# TestPoints.net
KiCad netlist of a schematic drawn in Altium Designer
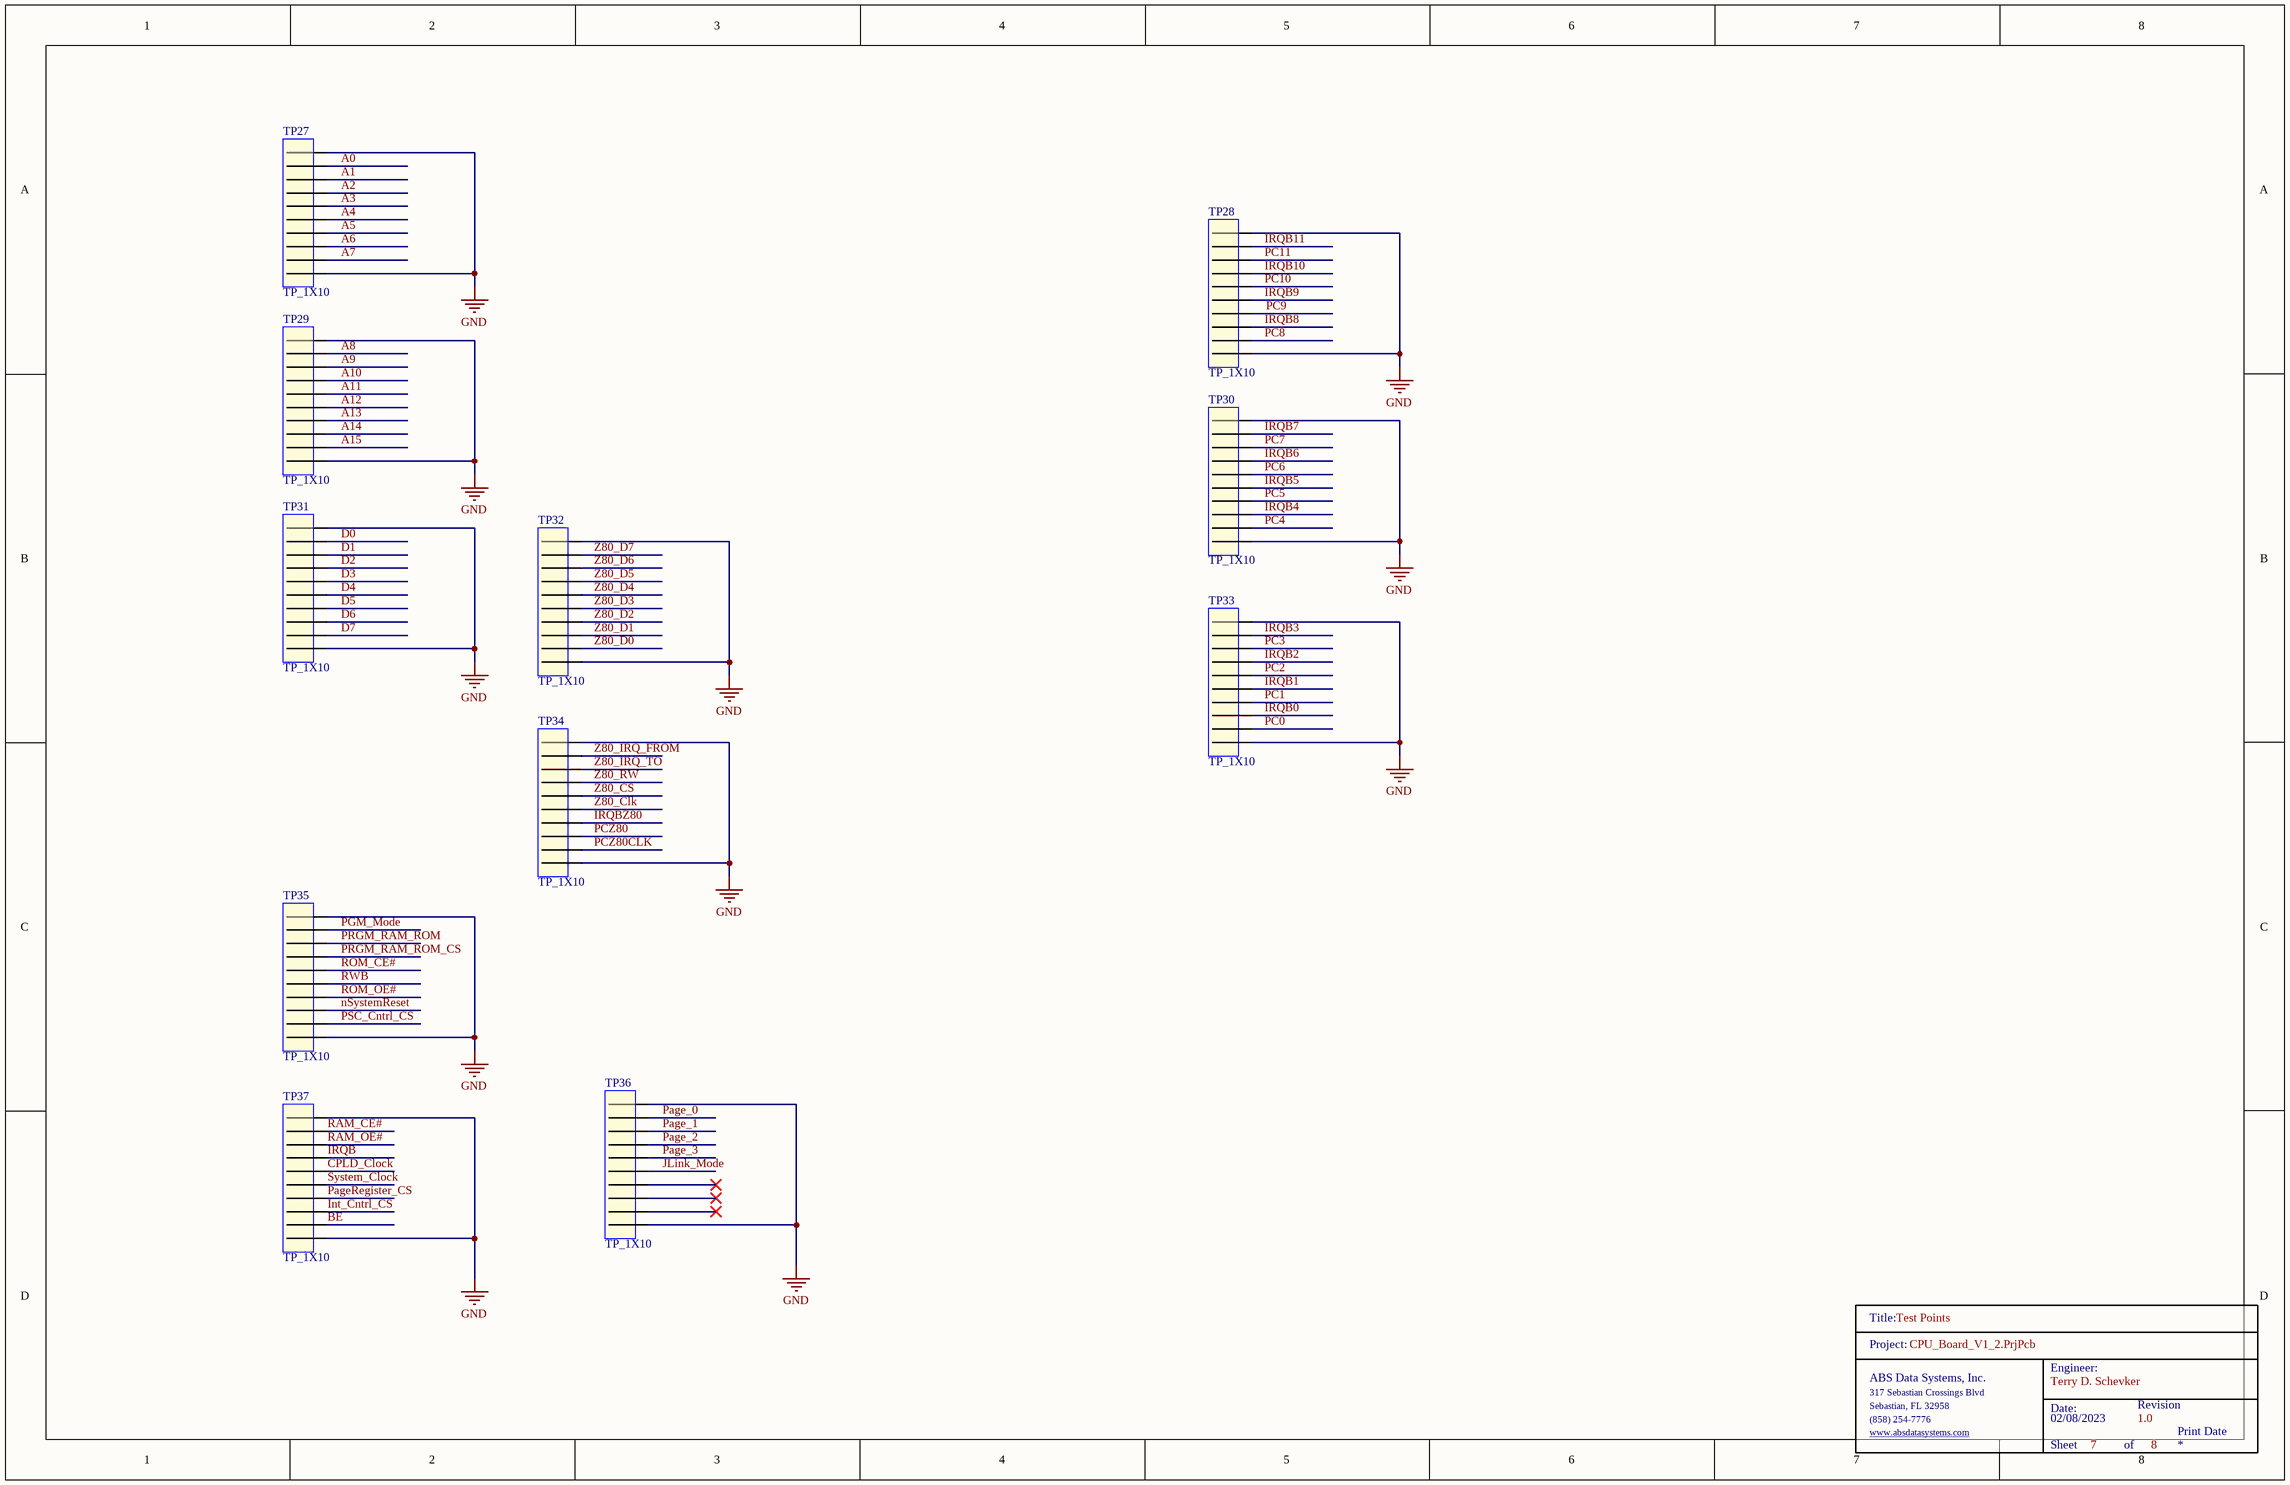
[diagram p0: TestPoints.SchDoc]

(export (version "E")
  (design (tool "Eeschema 10.0.6"))
  (components
    (comp (ref "TitleBlock_5") (value "TitleBlock") (libsource (lib "Misc") (part "TitleBlock")))
    (comp (ref "TP27")
      (value "TP_1X10")
      (footprint "TP_1X10")
      (fields
        (field (name "MANUFACTURER") "Samtec")
        (field (name "MANUFACTURER PART NUMBER") "TST-105-01-G-D")
      )
      (libsource (lib "Misc") (part "TP_1X10"))
    )
    (comp (ref "TP28")
      (value "TP_1X10")
      (footprint "TP_1X10")
      (fields
        (field (name "MANUFACTURER") "Samtec")
        (field (name "MANUFACTURER PART NUMBER") "TST-105-01-G-D")
      )
      (libsource (lib "Misc") (part "TP_1X10"))
    )
    (comp (ref "TP29")
      (value "TP_1X10")
      (footprint "TP_1X10")
      (fields
        (field (name "MANUFACTURER") "Samtec")
        (field (name "MANUFACTURER PART NUMBER") "TST-105-01-G-D")
      )
      (libsource (lib "Misc") (part "TP_1X10"))
    )
    (comp (ref "TP30")
      (value "TP_1X10")
      (footprint "TP_1X10")
      (fields
        (field (name "MANUFACTURER") "Samtec")
        (field (name "MANUFACTURER PART NUMBER") "TST-105-01-G-D")
      )
      (libsource (lib "Misc") (part "TP_1X10"))
    )
    (comp (ref "TP31")
      (value "TP_1X10")
      (footprint "TP_1X10")
      (fields
        (field (name "MANUFACTURER") "Samtec")
        (field (name "MANUFACTURER PART NUMBER") "TST-105-01-G-D")
      )
      (libsource (lib "Misc") (part "TP_1X10"))
    )
    (comp (ref "TP32")
      (value "TP_1X10")
      (footprint "TP_1X10")
      (fields
        (field (name "MANUFACTURER") "Samtec")
        (field (name "MANUFACTURER PART NUMBER") "TST-105-01-G-D")
      )
      (libsource (lib "Misc") (part "TP_1X10"))
    )
    (comp (ref "TP33")
      (value "TP_1X10")
      (footprint "TP_1X10")
      (fields
        (field (name "MANUFACTURER") "Samtec")
        (field (name "MANUFACTURER PART NUMBER") "TST-105-01-G-D")
      )
      (libsource (lib "Misc") (part "TP_1X10"))
    )
    (comp (ref "TP34")
      (value "TP_1X10")
      (footprint "TP_1X10")
      (fields
        (field (name "MANUFACTURER") "Samtec")
        (field (name "MANUFACTURER PART NUMBER") "TST-105-01-G-D")
      )
      (libsource (lib "Misc") (part "TP_1X10"))
    )
    (comp (ref "TP35")
      (value "TP_1X10")
      (footprint "TP_1X10")
      (fields
        (field (name "MANUFACTURER") "Samtec")
        (field (name "MANUFACTURER PART NUMBER") "TST-105-01-G-D")
      )
      (libsource (lib "Misc") (part "TP_1X10"))
    )
    (comp (ref "TP36")
      (value "TP_1X10")
      (footprint "TP_1X10")
      (fields
        (field (name "MANUFACTURER") "Samtec")
        (field (name "MANUFACTURER PART NUMBER") "TST-105-01-G-D")
      )
      (libsource (lib "Misc") (part "TP_1X10"))
    )
    (comp (ref "TP37")
      (value "TP_1X10")
      (footprint "TP_1X10")
      (fields
        (field (name "MANUFACTURER") "Samtec")
        (field (name "MANUFACTURER PART NUMBER") "TST-105-01-G-D")
      )
      (libsource (lib "Misc") (part "TP_1X10"))
    )
  )
  (nets
    (net (code "1") (name "/A0") (class "Default")
      (node (ref "TP27") (pin "2") (pinfunction "2_2") (pintype "passive"))
    )
    (net (code "2") (name "/A1") (class "Default")
      (node (ref "TP27") (pin "3") (pinfunction "3_3") (pintype "passive"))
    )
    (net (code "3") (name "/A2") (class "Default")
      (node (ref "TP27") (pin "4") (pinfunction "4_4") (pintype "passive"))
    )
    (net (code "4") (name "/A3") (class "Default")
      (node (ref "TP27") (pin "5") (pinfunction "5_5") (pintype "passive"))
    )
    (net (code "5") (name "/A4") (class "Default")
      (node (ref "TP27") (pin "6") (pinfunction "6_6") (pintype "passive"))
    )
    (net (code "6") (name "/A5") (class "Default")
      (node (ref "TP27") (pin "7") (pinfunction "7_7") (pintype "passive"))
    )
    (net (code "7") (name "/A6") (class "Default")
      (node (ref "TP27") (pin "8") (pinfunction "8_8") (pintype "passive"))
    )
    (net (code "8") (name "/A7") (class "Default")
      (node (ref "TP27") (pin "9") (pinfunction "9_9") (pintype "passive"))
    )
    (net (code "9") (name "/A8") (class "Default")
      (node (ref "TP29") (pin "2") (pinfunction "2_2") (pintype "passive"))
    )
    (net (code "10") (name "/A9") (class "Default")
      (node (ref "TP29") (pin "3") (pinfunction "3_3") (pintype "passive"))
    )
    (net (code "11") (name "/A10") (class "Default")
      (node (ref "TP29") (pin "4") (pinfunction "4_4") (pintype "passive"))
    )
    (net (code "12") (name "/A11") (class "Default")
      (node (ref "TP29") (pin "5") (pinfunction "5_5") (pintype "passive"))
    )
    (net (code "13") (name "/A12") (class "Default")
      (node (ref "TP29") (pin "6") (pinfunction "6_6") (pintype "passive"))
    )
    (net (code "14") (name "/A13") (class "Default")
      (node (ref "TP29") (pin "7") (pinfunction "7_7") (pintype "passive"))
    )
    (net (code "15") (name "/A14") (class "Default")
      (node (ref "TP29") (pin "8") (pinfunction "8_8") (pintype "passive"))
    )
    (net (code "16") (name "/A15") (class "Default")
      (node (ref "TP29") (pin "9") (pinfunction "9_9") (pintype "passive"))
    )
    (net (code "17") (name "/BE") (class "Default")
      (node (ref "TP37") (pin "9") (pinfunction "9_9") (pintype "passive"))
    )
    (net (code "18") (name "/CPLD_Clock") (class "Default")
      (node (ref "TP37") (pin "5") (pinfunction "5_5") (pintype "passive"))
    )
    (net (code "19") (name "/D0") (class "Default")
      (node (ref "TP31") (pin "2") (pinfunction "2_2") (pintype "passive"))
    )
    (net (code "20") (name "/D1") (class "Default")
      (node (ref "TP31") (pin "3") (pinfunction "3_3") (pintype "passive"))
    )
    (net (code "21") (name "/D2") (class "Default")
      (node (ref "TP31") (pin "4") (pinfunction "4_4") (pintype "passive"))
    )
    (net (code "22") (name "/D3") (class "Default")
      (node (ref "TP31") (pin "5") (pinfunction "5_5") (pintype "passive"))
    )
    (net (code "23") (name "/D4") (class "Default")
      (node (ref "TP31") (pin "6") (pinfunction "6_6") (pintype "passive"))
    )
    (net (code "24") (name "/D5") (class "Default")
      (node (ref "TP31") (pin "7") (pinfunction "7_7") (pintype "passive"))
    )
    (net (code "25") (name "/D6") (class "Default")
      (node (ref "TP31") (pin "8") (pinfunction "8_8") (pintype "passive"))
    )
    (net (code "26") (name "/D7") (class "Default")
      (node (ref "TP31") (pin "9") (pinfunction "9_9") (pintype "passive"))
    )
    (net (code "27") (name "/IRQB") (class "Default")
      (node (ref "TP37") (pin "4") (pinfunction "4_4") (pintype "passive"))
    )
    (net (code "28") (name "/IRQB0") (class "Default")
      (node (ref "TP33") (pin "8") (pinfunction "8_8") (pintype "passive"))
    )
    (net (code "29") (name "/IRQB1") (class "Default")
      (node (ref "TP33") (pin "6") (pinfunction "6_6") (pintype "passive"))
    )
    (net (code "30") (name "/IRQB2") (class "Default")
      (node (ref "TP33") (pin "4") (pinfunction "4_4") (pintype "passive"))
    )
    (net (code "31") (name "/IRQB3") (class "Default")
      (node (ref "TP33") (pin "2") (pinfunction "2_2") (pintype "passive"))
    )
    (net (code "32") (name "/IRQB4") (class "Default")
      (node (ref "TP30") (pin "8") (pinfunction "8_8") (pintype "passive"))
    )
    (net (code "33") (name "/IRQB5") (class "Default")
      (node (ref "TP30") (pin "6") (pinfunction "6_6") (pintype "passive"))
    )
    (net (code "34") (name "/IRQB6") (class "Default")
      (node (ref "TP30") (pin "4") (pinfunction "4_4") (pintype "passive"))
    )
    (net (code "35") (name "/IRQB7") (class "Default")
      (node (ref "TP30") (pin "2") (pinfunction "2_2") (pintype "passive"))
    )
    (net (code "36") (name "/IRQB8") (class "Default")
      (node (ref "TP28") (pin "8") (pinfunction "8_8") (pintype "passive"))
    )
    (net (code "37") (name "/IRQB9") (class "Default")
      (node (ref "TP28") (pin "6") (pinfunction "6_6") (pintype "passive"))
    )
    (net (code "38") (name "/IRQB10") (class "Default")
      (node (ref "TP28") (pin "4") (pinfunction "4_4") (pintype "passive"))
    )
    (net (code "39") (name "/IRQB11") (class "Default")
      (node (ref "TP28") (pin "2") (pinfunction "2_2") (pintype "passive"))
    )
    (net (code "40") (name "/IRQBZ80") (class "Default")
      (node (ref "TP34") (pin "7") (pinfunction "7_7") (pintype "passive"))
    )
    (net (code "41") (name "/Int_Cntrl_CS") (class "Default")
      (node (ref "TP37") (pin "8") (pinfunction "8_8") (pintype "passive"))
    )
    (net (code "42") (name "/JLink_Mode") (class "Default")
      (node (ref "TP36") (pin "6") (pinfunction "6_6") (pintype "passive"))
    )
    (net (code "43") (name "/PC0") (class "Default")
      (node (ref "TP33") (pin "9") (pinfunction "9_9") (pintype "passive"))
    )
    (net (code "44") (name "/PC1") (class "Default")
      (node (ref "TP33") (pin "7") (pinfunction "7_7") (pintype "passive"))
    )
    (net (code "45") (name "/PC2") (class "Default")
      (node (ref "TP33") (pin "5") (pinfunction "5_5") (pintype "passive"))
    )
    (net (code "46") (name "/PC3") (class "Default")
      (node (ref "TP33") (pin "3") (pinfunction "3_3") (pintype "passive"))
    )
    (net (code "47") (name "/PC4") (class "Default")
      (node (ref "TP30") (pin "9") (pinfunction "9_9") (pintype "passive"))
    )
    (net (code "48") (name "/PC5") (class "Default")
      (node (ref "TP30") (pin "7") (pinfunction "7_7") (pintype "passive"))
    )
    (net (code "49") (name "/PC6") (class "Default")
      (node (ref "TP30") (pin "5") (pinfunction "5_5") (pintype "passive"))
    )
    (net (code "50") (name "/PC7") (class "Default")
      (node (ref "TP30") (pin "3") (pinfunction "3_3") (pintype "passive"))
    )
    (net (code "51") (name "/PC8") (class "Default")
      (node (ref "TP28") (pin "9") (pinfunction "9_9") (pintype "passive"))
    )
    (net (code "52") (name "/PC9") (class "Default")
      (node (ref "TP28") (pin "7") (pinfunction "7_7") (pintype "passive"))
    )
    (net (code "53") (name "/PC10") (class "Default")
      (node (ref "TP28") (pin "5") (pinfunction "5_5") (pintype "passive"))
    )
    (net (code "54") (name "/PC11") (class "Default")
      (node (ref "TP28") (pin "3") (pinfunction "3_3") (pintype "passive"))
    )
    (net (code "55") (name "/PCZ80") (class "Default")
      (node (ref "TP34") (pin "8") (pinfunction "8_8") (pintype "passive"))
    )
    (net (code "56") (name "/PCZ80CLK") (class "Default")
      (node (ref "TP34") (pin "9") (pinfunction "9_9") (pintype "passive"))
    )
    (net (code "57") (name "/PGM_Mode") (class "Default")
      (node (ref "TP35") (pin "2") (pinfunction "2_2") (pintype "passive"))
    )
    (net (code "58") (name "/PRGM_RAM_ROM") (class "Default")
      (node (ref "TP35") (pin "3") (pinfunction "3_3") (pintype "passive"))
    )
    (net (code "59") (name "/PRGM_RAM_ROM_CS") (class "Default")
      (node (ref "TP35") (pin "4") (pinfunction "4_4") (pintype "passive"))
    )
    (net (code "60") (name "/PSC_Cntrl_CS") (class "Default")
      (node (ref "TP35") (pin "9") (pinfunction "9_9") (pintype "passive"))
    )
    (net (code "61") (name "/PageRegister_CS") (class "Default")
      (node (ref "TP37") (pin "7") (pinfunction "7_7") (pintype "passive"))
    )
    (net (code "62") (name "/Page_0") (class "Default")
      (node (ref "TP36") (pin "2") (pinfunction "2_2") (pintype "passive"))
    )
    (net (code "63") (name "/Page_1") (class "Default")
      (node (ref "TP36") (pin "3") (pinfunction "3_3") (pintype "passive"))
    )
    (net (code "64") (name "/Page_2") (class "Default")
      (node (ref "TP36") (pin "4") (pinfunction "4_4") (pintype "passive"))
    )
    (net (code "65") (name "/Page_3") (class "Default")
      (node (ref "TP36") (pin "5") (pinfunction "5_5") (pintype "passive"))
    )
    (net (code "66") (name "/RAM_CE#") (class "Default")
      (node (ref "TP37") (pin "2") (pinfunction "2_2") (pintype "passive"))
    )
    (net (code "67") (name "/RAM_OE#") (class "Default")
      (node (ref "TP37") (pin "3") (pinfunction "3_3") (pintype "passive"))
    )
    (net (code "68") (name "/ROM_CE#") (class "Default")
      (node (ref "TP35") (pin "5") (pinfunction "5_5") (pintype "passive"))
    )
    (net (code "69") (name "/ROM_OE#") (class "Default")
      (node (ref "TP35") (pin "7") (pinfunction "7_7") (pintype "passive"))
    )
    (net (code "70") (name "/RWB") (class "Default")
      (node (ref "TP35") (pin "6") (pinfunction "6_6") (pintype "passive"))
    )
    (net (code "71") (name "/System_Clock") (class "Default")
      (node (ref "TP37") (pin "6") (pinfunction "6_6") (pintype "passive"))
    )
    (net (code "72") (name "/Z80_CS") (class "Default")
      (node (ref "TP34") (pin "5") (pinfunction "5_5") (pintype "passive"))
    )
    (net (code "73") (name "/Z80_Clk") (class "Default")
      (node (ref "TP34") (pin "6") (pinfunction "6_6") (pintype "passive"))
    )
    (net (code "74") (name "/Z80_D0") (class "Default")
      (node (ref "TP32") (pin "9") (pinfunction "9_9") (pintype "passive"))
    )
    (net (code "75") (name "/Z80_D1") (class "Default")
      (node (ref "TP32") (pin "8") (pinfunction "8_8") (pintype "passive"))
    )
    (net (code "76") (name "/Z80_D2") (class "Default")
      (node (ref "TP32") (pin "7") (pinfunction "7_7") (pintype "passive"))
    )
    (net (code "77") (name "/Z80_D3") (class "Default")
      (node (ref "TP32") (pin "6") (pinfunction "6_6") (pintype "passive"))
    )
    (net (code "78") (name "/Z80_D4") (class "Default")
      (node (ref "TP32") (pin "5") (pinfunction "5_5") (pintype "passive"))
    )
    (net (code "79") (name "/Z80_D5") (class "Default")
      (node (ref "TP32") (pin "4") (pinfunction "4_4") (pintype "passive"))
    )
    (net (code "80") (name "/Z80_D6") (class "Default")
      (node (ref "TP32") (pin "3") (pinfunction "3_3") (pintype "passive"))
    )
    (net (code "81") (name "/Z80_D7") (class "Default")
      (node (ref "TP32") (pin "2") (pinfunction "2_2") (pintype "passive"))
    )
    (net (code "82") (name "/Z80_IRQ_FROM") (class "Default")
      (node (ref "TP34") (pin "2") (pinfunction "2_2") (pintype "passive"))
    )
    (net (code "83") (name "/Z80_IRQ_TO") (class "Default")
      (node (ref "TP34") (pin "3") (pinfunction "3_3") (pintype "passive"))
    )
    (net (code "84") (name "/Z80_RW") (class "Default")
      (node (ref "TP34") (pin "4") (pinfunction "4_4") (pintype "passive"))
    )
    (net (code "85") (name "/nSystemReset") (class "Default")
      (node (ref "TP35") (pin "8") (pinfunction "8_8") (pintype "passive"))
    )
    (net (code "86") (name "GND") (class "Default")
      (node (ref "TP27") (pin "1") (pinfunction "1_1") (pintype "passive"))
      (node (ref "TP27") (pin "10") (pinfunction "10_10") (pintype "passive"))
      (node (ref "TP28") (pin "1") (pinfunction "1_1") (pintype "passive"))
      (node (ref "TP28") (pin "10") (pinfunction "10_10") (pintype "passive"))
      (node (ref "TP29") (pin "1") (pinfunction "1_1") (pintype "passive"))
      (node (ref "TP29") (pin "10") (pinfunction "10_10") (pintype "passive"))
      (node (ref "TP30") (pin "1") (pinfunction "1_1") (pintype "passive"))
      (node (ref "TP30") (pin "10") (pinfunction "10_10") (pintype "passive"))
      (node (ref "TP31") (pin "1") (pinfunction "1_1") (pintype "passive"))
      (node (ref "TP31") (pin "10") (pinfunction "10_10") (pintype "passive"))
      (node (ref "TP32") (pin "1") (pinfunction "1_1") (pintype "passive"))
      (node (ref "TP32") (pin "10") (pinfunction "10_10") (pintype "passive"))
      (node (ref "TP33") (pin "1") (pinfunction "1_1") (pintype "passive"))
      (node (ref "TP33") (pin "10") (pinfunction "10_10") (pintype "passive"))
      (node (ref "TP34") (pin "1") (pinfunction "1_1") (pintype "passive"))
      (node (ref "TP34") (pin "10") (pinfunction "10_10") (pintype "passive"))
      (node (ref "TP35") (pin "1") (pinfunction "1_1") (pintype "passive"))
      (node (ref "TP35") (pin "10") (pinfunction "10_10") (pintype "passive"))
      (node (ref "TP36") (pin "1") (pinfunction "1_1") (pintype "passive"))
      (node (ref "TP36") (pin "10") (pinfunction "10_10") (pintype "passive"))
      (node (ref "TP37") (pin "1") (pinfunction "1_1") (pintype "passive"))
      (node (ref "TP37") (pin "10") (pinfunction "10_10") (pintype "passive"))
    )
    (net (code "87") (name "unconnected-(TP36-Pad7)") (class "Default")
      (node (ref "TP36") (pin "7") (pinfunction "7_7") (pintype "passive+no_connect"))
    )
    (net (code "88") (name "unconnected-(TP36-Pad8)") (class "Default")
      (node (ref "TP36") (pin "8") (pinfunction "8_8") (pintype "passive+no_connect"))
    )
    (net (code "89") (name "unconnected-(TP36-Pad9)") (class "Default")
      (node (ref "TP36") (pin "9") (pinfunction "9_9") (pintype "passive+no_connect"))
    )
  )
)
